# EasyEDA_Schematic_ES1050_T11Bees_Beehive.net
KiCad netlist of a schematic drawn in EasyEDA
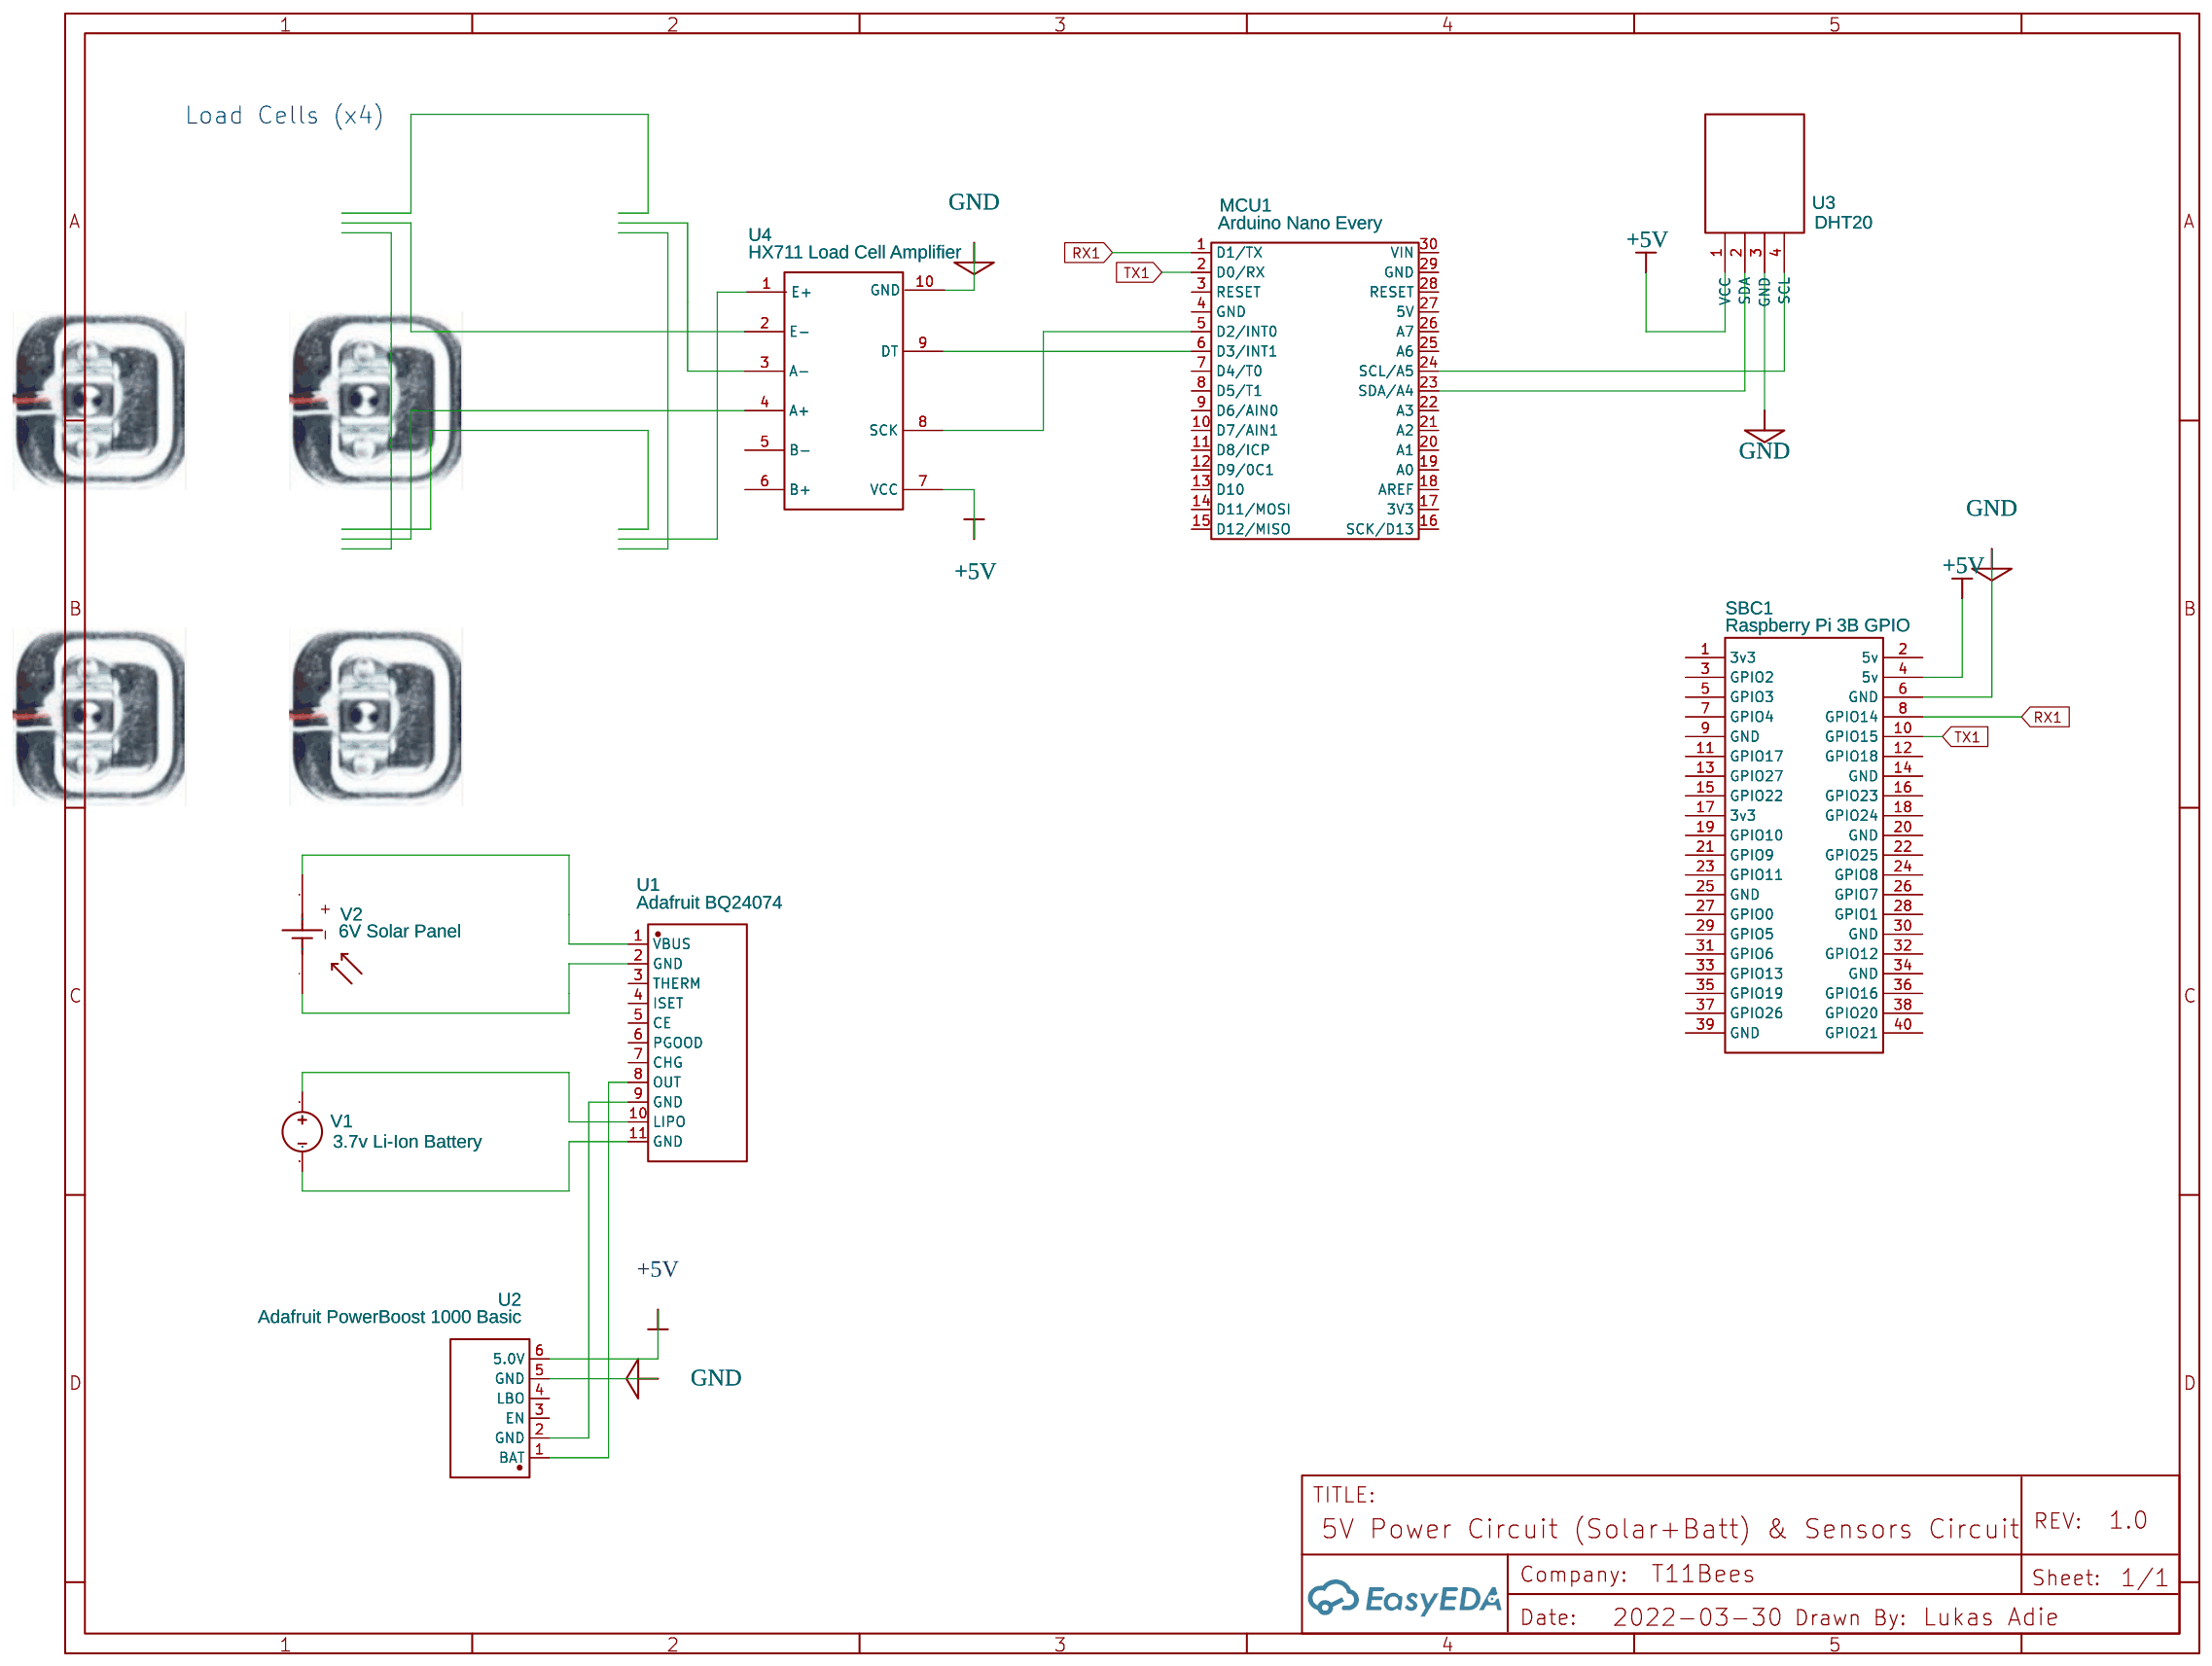
[diagram p0: schematic sheet]

(export (version "E")
  (design (tool "Eeschema 10.0.6"))
  (components
    (comp (ref "MCU1") (value "Arduino Nano Every") (libsource (lib "") (part "Arduino_Nano_Header")))
    (comp (ref "SBC1") (value "Raspberry Pi 3B GPIO") (libsource (lib "") (part "RPI3B+_HEADER COPY")))
    (comp (ref "U1") (value "Adafruit BQ24074") (libsource (lib "") (part "Adafruit BQ24074")))
    (comp (ref "U2")
      (value "Adafruit PowerBoost 1000 Basic")
      (libsource (lib "") (part "Adafruit PowerBoost 1000 Basic"))
    )
    (comp (ref "U3") (value "DHT20") (libsource (lib "") (part "AM2108_DHT20")))
    (comp (ref "U4")
      (value "HX711 Load Cell Amplifier")
      (fields (field (name "BOM_Manufacturer Part") "HX711"))
      (libsource (lib "") (part "LOADCELL_HX711"))
    )
    (comp (ref "V1") (value "3.7v Li-Ion Battery") (libsource (lib "") (part "VOLTAGE_SOURCE")))
    (comp (ref "V2") (value "6V Solar Panel") (libsource (lib "") (part "solar panel")))
  )
  (nets
    (net (code "1") (name "+5V") (class "Default")
      (node (ref "SBC1") (pin "4") (pinfunction "5v_4") (pintype "unspecified"))
      (node (ref "U2") (pin "6") (pinfunction "5.0V_6") (pintype "unspecified"))
      (node (ref "U3") (pin "1") (pinfunction "VCC_1") (pintype "unspecified"))
      (node (ref "U4") (pin "7") (pinfunction "VCC_7") (pintype "unspecified"))
    )
    (net (code "2") (name "GND") (class "Default")
      (node (ref "SBC1") (pin "6") (pinfunction "GND_6") (pintype "unspecified"))
      (node (ref "U2") (pin "5") (pinfunction "GND_5") (pintype "unspecified"))
      (node (ref "U3") (pin "3") (pinfunction "GND_3") (pintype "unspecified"))
      (node (ref "U4") (pin "10") (pinfunction "GND_10") (pintype "unspecified"))
    )
    (net (code "3") (name "Net-(MCU1-D2{slash}INT0)") (class "Default")
      (node (ref "MCU1") (pin "5") (pinfunction "D2/INT0_5") (pintype "unspecified"))
      (node (ref "U4") (pin "8") (pinfunction "SCK_8") (pintype "unspecified"))
    )
    (net (code "4") (name "Net-(MCU1-D3{slash}INT1)") (class "Default")
      (node (ref "MCU1") (pin "6") (pinfunction "D3/INT1_6") (pintype "unspecified"))
      (node (ref "U4") (pin "9") (pinfunction "DT_9") (pintype "unspecified"))
    )
    (net (code "5") (name "Net-(MCU1-SCL{slash}A5)") (class "Default")
      (node (ref "MCU1") (pin "24") (pinfunction "SCL/A5_24") (pintype "unspecified"))
      (node (ref "U3") (pin "4") (pinfunction "SCL_4") (pintype "unspecified"))
    )
    (net (code "6") (name "Net-(MCU1-SDA{slash}A4)") (class "Default")
      (node (ref "MCU1") (pin "23") (pinfunction "SDA/A4_23") (pintype "unspecified"))
      (node (ref "U3") (pin "2") (pinfunction "SDA_2") (pintype "unspecified"))
    )
    (net (code "7") (name "Net-(U1-GND-Pad9)") (class "Default")
      (node (ref "U1") (pin "9") (pinfunction "GND_9") (pintype "unspecified"))
      (node (ref "U2") (pin "2") (pinfunction "GND_2") (pintype "unspecified"))
    )
    (net (code "8") (name "Net-(U1-GND-Pad11)") (class "Default")
      (node (ref "U1") (pin "11") (pinfunction "GND_11") (pintype "unspecified"))
      (node (ref "V1") (pin "2") (pinfunction "2_2") (pintype "unspecified"))
    )
    (net (code "9") (name "Net-(U1-LIPO)") (class "Default")
      (node (ref "U1") (pin "10") (pinfunction "LIPO_10") (pintype "unspecified"))
      (node (ref "V1") (pin "1") (pinfunction "1_1") (pintype "unspecified"))
    )
    (net (code "10") (name "Net-(U1-OUT)") (class "Default")
      (node (ref "U1") (pin "8") (pinfunction "OUT_8") (pintype "unspecified"))
      (node (ref "U2") (pin "1") (pinfunction "BAT_1") (pintype "unspecified"))
    )
    (net (code "11") (name "Net-(U1-VBUS)") (class "Default")
      (node (ref "U1") (pin "1") (pinfunction "VBUS_1") (pintype "unspecified"))
      (node (ref "V2") (pin "+") (pinfunction "A_+") (pintype "unspecified"))
    )
    (net (code "12") (name "Net-(V2-C)") (class "Default")
      (node (ref "U1") (pin "2") (pinfunction "GND_2") (pintype "unspecified"))
      (node (ref "V2") (pin "-") (pinfunction "C_-") (pintype "unspecified"))
    )
    (net (code "13") (name "RX1") (class "Default")
      (node (ref "MCU1") (pin "1") (pinfunction "D1/TX_1") (pintype "unspecified"))
      (node (ref "SBC1") (pin "8") (pinfunction "GPIO14_8") (pintype "unspecified"))
    )
    (net (code "14") (name "TX1") (class "Default")
      (node (ref "MCU1") (pin "2") (pinfunction "D0/RX_2") (pintype "unspecified"))
      (node (ref "SBC1") (pin "10") (pinfunction "GPIO15_10") (pintype "unspecified"))
    )
    (net (code "15") (name "unconnected-(MCU1-3V3-Pad17)") (class "Default")
      (node (ref "MCU1") (pin "17") (pinfunction "3V3_17") (pintype "unspecified"))
    )
    (net (code "16") (name "unconnected-(MCU1-5V-Pad27)") (class "Default")
      (node (ref "MCU1") (pin "27") (pinfunction "5V_27") (pintype "unspecified"))
    )
    (net (code "17") (name "unconnected-(MCU1-A0-Pad19)") (class "Default")
      (node (ref "MCU1") (pin "19") (pinfunction "A0_19") (pintype "unspecified"))
    )
    (net (code "18") (name "unconnected-(MCU1-A1-Pad20)") (class "Default")
      (node (ref "MCU1") (pin "20") (pinfunction "A1_20") (pintype "unspecified"))
    )
    (net (code "19") (name "unconnected-(MCU1-A2-Pad21)") (class "Default")
      (node (ref "MCU1") (pin "21") (pinfunction "A2_21") (pintype "unspecified"))
    )
    (net (code "20") (name "unconnected-(MCU1-A3-Pad22)") (class "Default")
      (node (ref "MCU1") (pin "22") (pinfunction "A3_22") (pintype "unspecified"))
    )
    (net (code "21") (name "unconnected-(MCU1-A6-Pad25)") (class "Default")
      (node (ref "MCU1") (pin "25") (pinfunction "A6_25") (pintype "unspecified"))
    )
    (net (code "22") (name "unconnected-(MCU1-A7-Pad26)") (class "Default")
      (node (ref "MCU1") (pin "26") (pinfunction "A7_26") (pintype "unspecified"))
    )
    (net (code "23") (name "unconnected-(MCU1-AREF-Pad18)") (class "Default")
      (node (ref "MCU1") (pin "18") (pinfunction "AREF_18") (pintype "unspecified"))
    )
    (net (code "24") (name "unconnected-(MCU1-D4{slash}T0-Pad7)") (class "Default")
      (node (ref "MCU1") (pin "7") (pinfunction "D4/T0_7") (pintype "unspecified"))
    )
    (net (code "25") (name "unconnected-(MCU1-D5{slash}T1-Pad8)") (class "Default")
      (node (ref "MCU1") (pin "8") (pinfunction "D5/T1_8") (pintype "unspecified"))
    )
    (net (code "26") (name "unconnected-(MCU1-D6{slash}AIN0-Pad9)") (class "Default")
      (node (ref "MCU1") (pin "9") (pinfunction "D6/AIN0_9") (pintype "unspecified"))
    )
    (net (code "27") (name "unconnected-(MCU1-D7{slash}AIN1-Pad10)") (class "Default")
      (node (ref "MCU1") (pin "10") (pinfunction "D7/AIN1_10") (pintype "unspecified"))
    )
    (net (code "28") (name "unconnected-(MCU1-D8{slash}ICP-Pad11)") (class "Default")
      (node (ref "MCU1") (pin "11") (pinfunction "D8/ICP_11") (pintype "unspecified"))
    )
    (net (code "29") (name "unconnected-(MCU1-D9{slash}0C1-Pad12)") (class "Default")
      (node (ref "MCU1") (pin "12") (pinfunction "D9/0C1_12") (pintype "unspecified"))
    )
    (net (code "30") (name "unconnected-(MCU1-D10-Pad13)") (class "Default")
      (node (ref "MCU1") (pin "13") (pinfunction "D10_13") (pintype "unspecified"))
    )
    (net (code "31") (name "unconnected-(MCU1-D11{slash}MOSI-Pad14)") (class "Default")
      (node (ref "MCU1") (pin "14") (pinfunction "D11/MOSI_14") (pintype "unspecified"))
    )
    (net (code "32") (name "unconnected-(MCU1-D12{slash}MISO-Pad15)") (class "Default")
      (node (ref "MCU1") (pin "15") (pinfunction "D12/MISO_15") (pintype "unspecified"))
    )
    (net (code "33") (name "unconnected-(MCU1-GND-Pad4)") (class "Default")
      (node (ref "MCU1") (pin "4") (pinfunction "GND_4") (pintype "unspecified"))
    )
    (net (code "34") (name "unconnected-(MCU1-GND-Pad29)") (class "Default")
      (node (ref "MCU1") (pin "29") (pinfunction "GND_29") (pintype "unspecified"))
    )
    (net (code "35") (name "unconnected-(MCU1-RESET-Pad3)") (class "Default")
      (node (ref "MCU1") (pin "3") (pinfunction "RESET_3") (pintype "unspecified"))
    )
    (net (code "36") (name "unconnected-(MCU1-RESET-Pad28)") (class "Default")
      (node (ref "MCU1") (pin "28") (pinfunction "RESET_28") (pintype "unspecified"))
    )
    (net (code "37") (name "unconnected-(MCU1-SCK{slash}D13-Pad16)") (class "Default")
      (node (ref "MCU1") (pin "16") (pinfunction "SCK/D13_16") (pintype "unspecified"))
    )
    (net (code "38") (name "unconnected-(MCU1-VIN-Pad30)") (class "Default")
      (node (ref "MCU1") (pin "30") (pinfunction "VIN_30") (pintype "unspecified"))
    )
    (net (code "39") (name "unconnected-(SBC1-3v3-Pad1)") (class "Default")
      (node (ref "SBC1") (pin "1") (pinfunction "3v3_1") (pintype "unspecified"))
    )
    (net (code "40") (name "unconnected-(SBC1-3v3-Pad17)") (class "Default")
      (node (ref "SBC1") (pin "17") (pinfunction "3v3_17") (pintype "unspecified"))
    )
    (net (code "41") (name "unconnected-(SBC1-5v-Pad2)") (class "Default")
      (node (ref "SBC1") (pin "2") (pinfunction "5v_2") (pintype "unspecified"))
    )
    (net (code "42") (name "unconnected-(SBC1-GND-Pad9)") (class "Default")
      (node (ref "SBC1") (pin "9") (pinfunction "GND_9") (pintype "unspecified"))
    )
    (net (code "43") (name "unconnected-(SBC1-GND-Pad14)") (class "Default")
      (node (ref "SBC1") (pin "14") (pinfunction "GND_14") (pintype "unspecified"))
    )
    (net (code "44") (name "unconnected-(SBC1-GND-Pad20)") (class "Default")
      (node (ref "SBC1") (pin "20") (pinfunction "GND_20") (pintype "unspecified"))
    )
    (net (code "45") (name "unconnected-(SBC1-GND-Pad25)") (class "Default")
      (node (ref "SBC1") (pin "25") (pinfunction "GND_25") (pintype "unspecified"))
    )
    (net (code "46") (name "unconnected-(SBC1-GND-Pad30)") (class "Default")
      (node (ref "SBC1") (pin "30") (pinfunction "GND_30") (pintype "unspecified"))
    )
    (net (code "47") (name "unconnected-(SBC1-GND-Pad34)") (class "Default")
      (node (ref "SBC1") (pin "34") (pinfunction "GND_34") (pintype "unspecified"))
    )
    (net (code "48") (name "unconnected-(SBC1-GND-Pad39)") (class "Default")
      (node (ref "SBC1") (pin "39") (pinfunction "GND_39") (pintype "unspecified"))
    )
    (net (code "49") (name "unconnected-(SBC1-GPIO0-Pad27)") (class "Default")
      (node (ref "SBC1") (pin "27") (pinfunction "GPIO0_27") (pintype "unspecified"))
    )
    (net (code "50") (name "unconnected-(SBC1-GPIO1-Pad28)") (class "Default")
      (node (ref "SBC1") (pin "28") (pinfunction "GPIO1_28") (pintype "unspecified"))
    )
    (net (code "51") (name "unconnected-(SBC1-GPIO2-Pad3)") (class "Default")
      (node (ref "SBC1") (pin "3") (pinfunction "GPIO2_3") (pintype "unspecified"))
    )
    (net (code "52") (name "unconnected-(SBC1-GPIO3-Pad5)") (class "Default")
      (node (ref "SBC1") (pin "5") (pinfunction "GPIO3_5") (pintype "unspecified"))
    )
    (net (code "53") (name "unconnected-(SBC1-GPIO4-Pad7)") (class "Default")
      (node (ref "SBC1") (pin "7") (pinfunction "GPIO4_7") (pintype "unspecified"))
    )
    (net (code "54") (name "unconnected-(SBC1-GPIO5-Pad29)") (class "Default")
      (node (ref "SBC1") (pin "29") (pinfunction "GPIO5_29") (pintype "unspecified"))
    )
    (net (code "55") (name "unconnected-(SBC1-GPIO6-Pad31)") (class "Default")
      (node (ref "SBC1") (pin "31") (pinfunction "GPIO6_31") (pintype "unspecified"))
    )
    (net (code "56") (name "unconnected-(SBC1-GPIO7-Pad26)") (class "Default")
      (node (ref "SBC1") (pin "26") (pinfunction "GPIO7_26") (pintype "unspecified"))
    )
    (net (code "57") (name "unconnected-(SBC1-GPIO8-Pad24)") (class "Default")
      (node (ref "SBC1") (pin "24") (pinfunction "GPIO8_24") (pintype "unspecified"))
    )
    (net (code "58") (name "unconnected-(SBC1-GPIO9-Pad21)") (class "Default")
      (node (ref "SBC1") (pin "21") (pinfunction "GPIO9_21") (pintype "unspecified"))
    )
    (net (code "59") (name "unconnected-(SBC1-GPIO10-Pad19)") (class "Default")
      (node (ref "SBC1") (pin "19") (pinfunction "GPIO10_19") (pintype "unspecified"))
    )
    (net (code "60") (name "unconnected-(SBC1-GPIO11-Pad23)") (class "Default")
      (node (ref "SBC1") (pin "23") (pinfunction "GPIO11_23") (pintype "unspecified"))
    )
    (net (code "61") (name "unconnected-(SBC1-GPIO12-Pad32)") (class "Default")
      (node (ref "SBC1") (pin "32") (pinfunction "GPIO12_32") (pintype "unspecified"))
    )
    (net (code "62") (name "unconnected-(SBC1-GPIO13-Pad33)") (class "Default")
      (node (ref "SBC1") (pin "33") (pinfunction "GPIO13_33") (pintype "unspecified"))
    )
    (net (code "63") (name "unconnected-(SBC1-GPIO16-Pad36)") (class "Default")
      (node (ref "SBC1") (pin "36") (pinfunction "GPIO16_36") (pintype "unspecified"))
    )
    (net (code "64") (name "unconnected-(SBC1-GPIO17-Pad11)") (class "Default")
      (node (ref "SBC1") (pin "11") (pinfunction "GPIO17_11") (pintype "unspecified"))
    )
    (net (code "65") (name "unconnected-(SBC1-GPIO18-Pad12)") (class "Default")
      (node (ref "SBC1") (pin "12") (pinfunction "GPIO18_12") (pintype "unspecified"))
    )
    (net (code "66") (name "unconnected-(SBC1-GPIO19-Pad35)") (class "Default")
      (node (ref "SBC1") (pin "35") (pinfunction "GPIO19_35") (pintype "unspecified"))
    )
    (net (code "67") (name "unconnected-(SBC1-GPIO20-Pad38)") (class "Default")
      (node (ref "SBC1") (pin "38") (pinfunction "GPIO20_38") (pintype "unspecified"))
    )
    (net (code "68") (name "unconnected-(SBC1-GPIO21-Pad40)") (class "Default")
      (node (ref "SBC1") (pin "40") (pinfunction "GPIO21_40") (pintype "unspecified"))
    )
    (net (code "69") (name "unconnected-(SBC1-GPIO22-Pad15)") (class "Default")
      (node (ref "SBC1") (pin "15") (pinfunction "GPIO22_15") (pintype "unspecified"))
    )
    (net (code "70") (name "unconnected-(SBC1-GPIO23-Pad16)") (class "Default")
      (node (ref "SBC1") (pin "16") (pinfunction "GPIO23_16") (pintype "unspecified"))
    )
    (net (code "71") (name "unconnected-(SBC1-GPIO24-Pad18)") (class "Default")
      (node (ref "SBC1") (pin "18") (pinfunction "GPIO24_18") (pintype "unspecified"))
    )
    (net (code "72") (name "unconnected-(SBC1-GPIO25-Pad22)") (class "Default")
      (node (ref "SBC1") (pin "22") (pinfunction "GPIO25_22") (pintype "unspecified"))
    )
    (net (code "73") (name "unconnected-(SBC1-GPIO26-Pad37)") (class "Default")
      (node (ref "SBC1") (pin "37") (pinfunction "GPIO26_37") (pintype "unspecified"))
    )
    (net (code "74") (name "unconnected-(SBC1-GPIO27-Pad13)") (class "Default")
      (node (ref "SBC1") (pin "13") (pinfunction "GPIO27_13") (pintype "unspecified"))
    )
    (net (code "75") (name "unconnected-(U1-CE-Pad5)") (class "Default")
      (node (ref "U1") (pin "5") (pinfunction "CE_5") (pintype "unspecified"))
    )
    (net (code "76") (name "unconnected-(U1-CHG-Pad7)") (class "Default")
      (node (ref "U1") (pin "7") (pinfunction "CHG_7") (pintype "unspecified"))
    )
    (net (code "77") (name "unconnected-(U1-ISET-Pad4)") (class "Default")
      (node (ref "U1") (pin "4") (pinfunction "ISET_4") (pintype "unspecified"))
    )
    (net (code "78") (name "unconnected-(U1-PGOOD-Pad6)") (class "Default")
      (node (ref "U1") (pin "6") (pinfunction "PGOOD_6") (pintype "unspecified"))
    )
    (net (code "79") (name "unconnected-(U1-THERM-Pad3)") (class "Default")
      (node (ref "U1") (pin "3") (pinfunction "THERM_3") (pintype "unspecified"))
    )
    (net (code "80") (name "unconnected-(U2-EN-Pad3)") (class "Default")
      (node (ref "U2") (pin "3") (pinfunction "EN_3") (pintype "unspecified"))
    )
    (net (code "81") (name "unconnected-(U2-LBO-Pad4)") (class "Default")
      (node (ref "U2") (pin "4") (pinfunction "LBO_4") (pintype "unspecified"))
    )
    (net (code "82") (name "unconnected-(U4-A+-Pad4)") (class "Default")
      (node (ref "U4") (pin "4") (pinfunction "A+_4") (pintype "unspecified"))
    )
    (net (code "83") (name "unconnected-(U4-A--Pad3)") (class "Default")
      (node (ref "U4") (pin "3") (pinfunction "A-_3") (pintype "unspecified"))
    )
    (net (code "84") (name "unconnected-(U4-B+-Pad6)") (class "Default")
      (node (ref "U4") (pin "6") (pinfunction "B+_6") (pintype "unspecified"))
    )
    (net (code "85") (name "unconnected-(U4-B--Pad5)") (class "Default")
      (node (ref "U4") (pin "5") (pinfunction "B-_5") (pintype "unspecified"))
    )
    (net (code "86") (name "unconnected-(U4-E+-Pad1)") (class "Default")
      (node (ref "U4") (pin "1") (pinfunction "E+_1") (pintype "unspecified"))
    )
    (net (code "87") (name "unconnected-(U4-E--Pad2)") (class "Default")
      (node (ref "U4") (pin "2") (pinfunction "E-_2") (pintype "unspecified"))
    )
  )
)
